# PDV.net
KiCad netlist of a schematic drawn in EAGLE
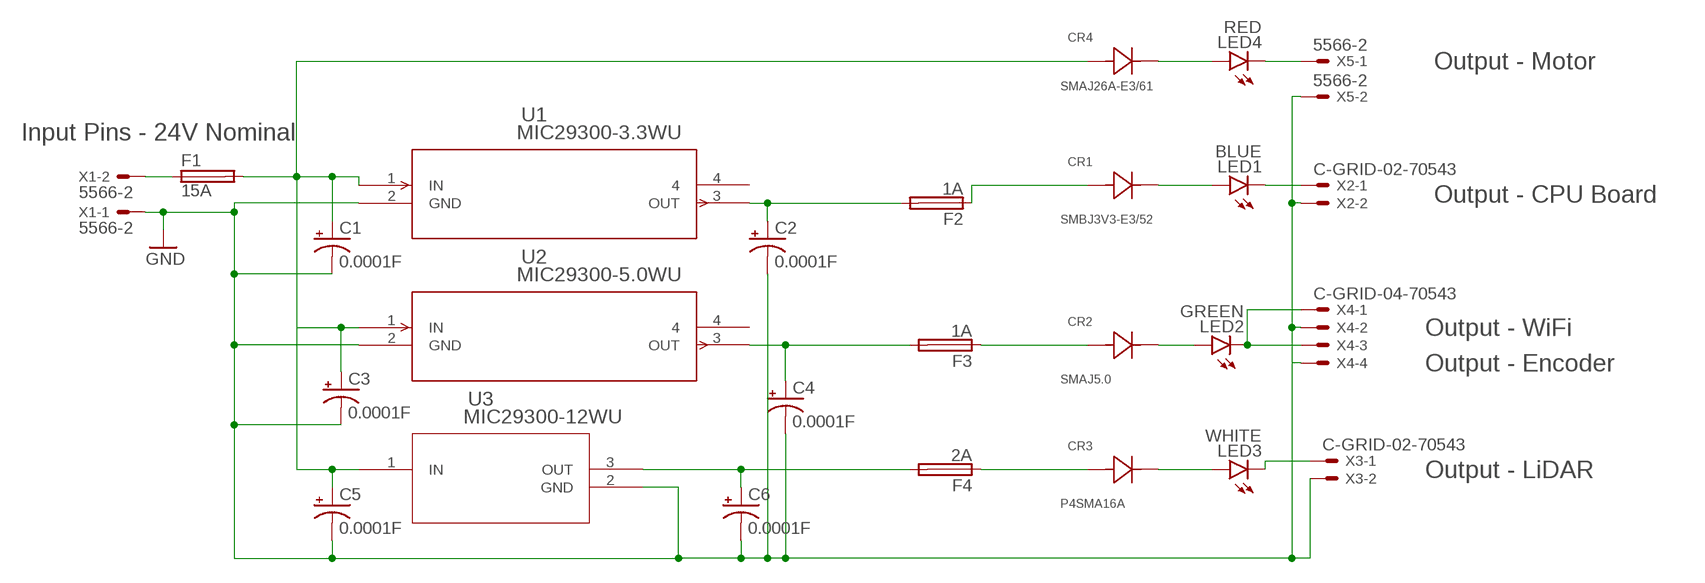
[diagram p0: schematic, sheet 1]

(export (version "E")
  (design (tool "Eeschema 10.0.6"))
  (components
    (comp (ref "C1")
      (value "0.0001F")
      (footprint "eagle-import:E2,5-6")
      (libsource (lib "eagle-import") (part "CPOL-USE2.5-6"))
    )
    (comp (ref "C2")
      (value "0.0001F")
      (footprint "eagle-import:E2,5-6")
      (libsource (lib "eagle-import") (part "CPOL-USE2.5-6"))
    )
    (comp (ref "C3")
      (value "0.0001F")
      (footprint "eagle-import:E2,5-6")
      (libsource (lib "eagle-import") (part "CPOL-USE2.5-6"))
    )
    (comp (ref "C4")
      (value "0.0001F")
      (footprint "eagle-import:E2,5-6")
      (libsource (lib "eagle-import") (part "CPOL-USE2.5-6"))
    )
    (comp (ref "C5")
      (value "0.0001F")
      (footprint "eagle-import:E2,5-6")
      (libsource (lib "eagle-import") (part "CPOL-USE2.5-6"))
    )
    (comp (ref "C6")
      (value "0.0001F")
      (footprint "eagle-import:E2,5-6")
      (libsource (lib "eagle-import") (part "CPOL-USE2.5-6"))
    )
    (comp (ref "CR1")
      (value "SMBJ3V3-E3/52")
      (footprint "eagle-import:CR_V3-E3_52_VIS")
      (fields (field (name "COPYRIGHT") "Copyright (C) 2025 Ultra Librarian. All rights reserved."))
      (libsource (lib "eagle-import") (part "SMBJ3V3-E3/52"))
    )
    (comp (ref "CR2")
      (value "SMAJ5.0")
      (footprint "eagle-import:SMASERIES_LTF")
      (fields (field (name "COPYRIGHT") "Copyright (C) 2025 Ultra Librarian. All rights reserved."))
      (libsource (lib "eagle-import") (part "SMAJ5.0"))
    )
    (comp (ref "CR3")
      (value "P4SMA16A")
      (footprint "eagle-import:P4SMASERIES_LTF")
      (fields (field (name "COPYRIGHT") "Copyright (C) 2025 Ultra Librarian. All rights reserved."))
      (libsource (lib "eagle-import") (part "P4SMA16A"))
    )
    (comp (ref "CR4")
      (value "SMAJ26A-E3/61")
      (footprint "eagle-import:DIODE_DO-214AC")
      (fields (field (name "COPYRIGHT") "Copyright (C) 2025 Ultra Librarian. All rights reserved."))
      (libsource (lib "eagle-import") (part "SMAJ26A-E3/61"))
    )
    (comp (ref "F1")
      (value "15A")
      (footprint "eagle-import:TE5")
      (libsource (lib "eagle-import") (part "TE5"))
    )
    (comp (ref "F2")
      (value "1A")
      (footprint "eagle-import:TE5")
      (libsource (lib "eagle-import") (part "TE5"))
    )
    (comp (ref "F3")
      (value "1A")
      (footprint "eagle-import:TE5")
      (libsource (lib "eagle-import") (part "TE5"))
    )
    (comp (ref "F4")
      (value "2A")
      (footprint "eagle-import:TE5")
      (libsource (lib "eagle-import") (part "TE5"))
    )
    (comp (ref "LED1")
      (value "BLUE")
      (footprint "eagle-import:1206")
      (libsource (lib "eagle-import") (part "LEDSMT1206"))
    )
    (comp (ref "LED2")
      (value "GREEN")
      (footprint "eagle-import:1206")
      (libsource (lib "eagle-import") (part "LEDSMT1206"))
    )
    (comp (ref "LED3")
      (value "WHITE")
      (footprint "eagle-import:1206")
      (libsource (lib "eagle-import") (part "LEDSMT1206"))
    )
    (comp (ref "LED4")
      (value "RED")
      (footprint "eagle-import:1206")
      (libsource (lib "eagle-import") (part "LEDSMT1206"))
    )
    (comp (ref "U1")
      (value "MIC29300-3.3WU")
      (footprint "eagle-import:TO-263-3_MCL")
      (fields (field (name "COPYRIGHT") "Copyright (C) 2025 Ultra Librarian. All rights reserved."))
      (libsource (lib "eagle-import") (part "MIC29300-3.3WU"))
    )
    (comp (ref "U2")
      (value "MIC29300-5.0WU")
      (footprint "eagle-import:TO-263-3_MCL")
      (fields (field (name "COPYRIGHT") "Copyright (C) 2025 Ultra Librarian. All rights reserved."))
      (libsource (lib "eagle-import") (part "MIC29300-5.0WU"))
    )
    (comp (ref "U3")
      (value "MIC29300-12WU")
      (footprint "eagle-import:TO220-3LD-PL-1_MCH")
      (fields (field (name "COPYRIGHT") "Copyright (C) 2025 Ultra Librarian. All rights reserved."))
      (libsource (lib "eagle-import") (part "MIC29300-12WU"))
    )
    (comp (ref "X1")
      (value "5566-2")
      (footprint "eagle-import:5566-2")
      (fields (field (name "MF") "MOLEX"))
      (libsource (lib "eagle-import") (part "5566-2"))
    )
    (comp (ref "X2")
      (value "C-GRID-02-70543")
      (footprint "eagle-import:70543-02")
      (fields (field (name "MF") "MOLEX"))
      (libsource (lib "eagle-import") (part "C-GRID-02-70543"))
    )
    (comp (ref "X3")
      (value "C-GRID-02-70543")
      (footprint "eagle-import:70543-02")
      (fields (field (name "MF") "MOLEX"))
      (libsource (lib "eagle-import") (part "C-GRID-02-70543"))
    )
    (comp (ref "X4")
      (value "C-GRID-04-70543")
      (footprint "eagle-import:70543-04")
      (fields (field (name "MF") "MOLEX"))
      (libsource (lib "eagle-import") (part "C-GRID-04-70543"))
    )
    (comp (ref "X5")
      (value "5566-2")
      (footprint "eagle-import:5566-2")
      (fields (field (name "MF") "MOLEX"))
      (libsource (lib "eagle-import") (part "5566-2"))
    )
  )
  (nets
    (net (code "1") (name "GND") (class "Default")
      (node (ref "C1") (pin "-") (pinfunction "-_-") (pintype "passive"))
      (node (ref "C2") (pin "-") (pinfunction "-_-") (pintype "passive"))
      (node (ref "C3") (pin "-") (pinfunction "-_-") (pintype "passive"))
      (node (ref "C4") (pin "-") (pinfunction "-_-") (pintype "passive"))
      (node (ref "C5") (pin "-") (pinfunction "-_-") (pintype "passive"))
      (node (ref "C6") (pin "-") (pinfunction "-_-") (pintype "passive"))
      (node (ref "U1") (pin "2") (pinfunction "GND_2") (pintype "power_in"))
      (node (ref "U2") (pin "2") (pinfunction "GND_2") (pintype "power_in"))
      (node (ref "U3") (pin "2") (pinfunction "GND_2") (pintype "passive"))
      (node (ref "X1") (pin "1") (pinfunction "S_1") (pintype "passive"))
      (node (ref "X2") (pin "2") (pinfunction "S_2") (pintype "passive"))
      (node (ref "X3") (pin "2") (pinfunction "S_2") (pintype "passive"))
      (node (ref "X4") (pin "2") (pinfunction "S_2") (pintype "passive"))
      (node (ref "X4") (pin "4") (pinfunction "S_4") (pintype "passive"))
      (node (ref "X5") (pin "2") (pinfunction "S_2") (pintype "passive"))
    )
    (net (code "2") (name "Net-(CR1-Pad1)") (class "Default")
      (node (ref "CR1") (pin "1") (pinfunction "1_1") (pintype "passive"))
      (node (ref "LED1") (pin "A") (pinfunction "A_A") (pintype "passive"))
    )
    (net (code "3") (name "Net-(CR1-Pad2)") (class "Default")
      (node (ref "CR1") (pin "2") (pinfunction "2_2") (pintype "passive"))
      (node (ref "F2") (pin "1") (pinfunction "1_1") (pintype "passive"))
    )
    (net (code "4") (name "Net-(CR2-Pad1)") (class "Default")
      (node (ref "CR2") (pin "1") (pinfunction "1_1") (pintype "passive"))
      (node (ref "LED2") (pin "A") (pinfunction "A_A") (pintype "passive"))
    )
    (net (code "5") (name "Net-(CR2-Pad2)") (class "Default")
      (node (ref "CR2") (pin "2") (pinfunction "2_2") (pintype "passive"))
      (node (ref "F3") (pin "1") (pinfunction "1_1") (pintype "passive"))
    )
    (net (code "6") (name "Net-(CR3-Pad1)") (class "Default")
      (node (ref "CR3") (pin "1") (pinfunction "1_1") (pintype "passive"))
      (node (ref "LED3") (pin "A") (pinfunction "A_A") (pintype "passive"))
    )
    (net (code "7") (name "Net-(CR3-Pad2)") (class "Default")
      (node (ref "CR3") (pin "2") (pinfunction "2_2") (pintype "passive"))
      (node (ref "F4") (pin "1") (pinfunction "1_1") (pintype "passive"))
    )
    (net (code "8") (name "Net-(CR4-Pad1)") (class "Default")
      (node (ref "CR4") (pin "1") (pinfunction "1_1") (pintype "passive"))
      (node (ref "LED4") (pin "A") (pinfunction "A_A") (pintype "passive"))
    )
    (net (code "9") (name "Net-(U1-IN)") (class "Default")
      (node (ref "C1") (pin "+") (pinfunction "+_+") (pintype "passive"))
      (node (ref "C3") (pin "+") (pinfunction "+_+") (pintype "passive"))
      (node (ref "C5") (pin "+") (pinfunction "+_+") (pintype "passive"))
      (node (ref "CR4") (pin "2") (pinfunction "2_2") (pintype "passive"))
      (node (ref "F1") (pin "2") (pinfunction "2_2") (pintype "passive"))
      (node (ref "U1") (pin "1") (pinfunction "IN_1") (pintype "input"))
      (node (ref "U2") (pin "1") (pinfunction "IN_1") (pintype "input"))
      (node (ref "U3") (pin "1") (pinfunction "IN_1") (pintype "input"))
    )
    (net (code "10") (name "Net-(U1-OUT)") (class "Default")
      (node (ref "C2") (pin "+") (pinfunction "+_+") (pintype "passive"))
      (node (ref "F2") (pin "2") (pinfunction "2_2") (pintype "passive"))
      (node (ref "U1") (pin "3") (pinfunction "OUT_3") (pintype "output"))
    )
    (net (code "11") (name "Net-(U2-OUT)") (class "Default")
      (node (ref "C4") (pin "+") (pinfunction "+_+") (pintype "passive"))
      (node (ref "F3") (pin "2") (pinfunction "2_2") (pintype "passive"))
      (node (ref "U2") (pin "3") (pinfunction "OUT_3") (pintype "output"))
    )
    (net (code "12") (name "Net-(U3-OUT)") (class "Default")
      (node (ref "C6") (pin "+") (pinfunction "+_+") (pintype "passive"))
      (node (ref "F4") (pin "2") (pinfunction "2_2") (pintype "passive"))
      (node (ref "U3") (pin "3") (pinfunction "OUT_3") (pintype "output"))
    )
    (net (code "13") (name "Net-(X1B-S)") (class "Default")
      (node (ref "F1") (pin "1") (pinfunction "1_1") (pintype "passive"))
      (node (ref "X1") (pin "2") (pinfunction "S_2") (pintype "passive"))
    )
    (net (code "14") (name "Net-(X2A-S)") (class "Default")
      (node (ref "LED1") (pin "C") (pinfunction "C_C") (pintype "passive"))
      (node (ref "X2") (pin "1") (pinfunction "S_1") (pintype "passive"))
    )
    (net (code "15") (name "Net-(X3A-S)") (class "Default")
      (node (ref "LED3") (pin "C") (pinfunction "C_C") (pintype "passive"))
      (node (ref "X3") (pin "1") (pinfunction "S_1") (pintype "passive"))
    )
    (net (code "16") (name "Net-(X4A-S)") (class "Default")
      (node (ref "LED2") (pin "C") (pinfunction "C_C") (pintype "passive"))
      (node (ref "X4") (pin "1") (pinfunction "S_1") (pintype "passive"))
      (node (ref "X4") (pin "3") (pinfunction "S_3") (pintype "passive"))
    )
    (net (code "17") (name "Net-(X5A-S)") (class "Default")
      (node (ref "LED4") (pin "C") (pinfunction "C_C") (pintype "passive"))
      (node (ref "X5") (pin "1") (pinfunction "S_1") (pintype "passive"))
    )
    (net (code "18") (name "unconnected-(U1-Pad4)") (class "Default")
      (node (ref "U1") (pin "4") (pinfunction "4_4") (pintype "passive"))
    )
    (net (code "19") (name "unconnected-(U2-Pad4)") (class "Default")
      (node (ref "U2") (pin "4") (pinfunction "4_4") (pintype "passive"))
    )
  )
)
